# Delibird.net
KiCad netlist of a schematic drawn in Altium Designer
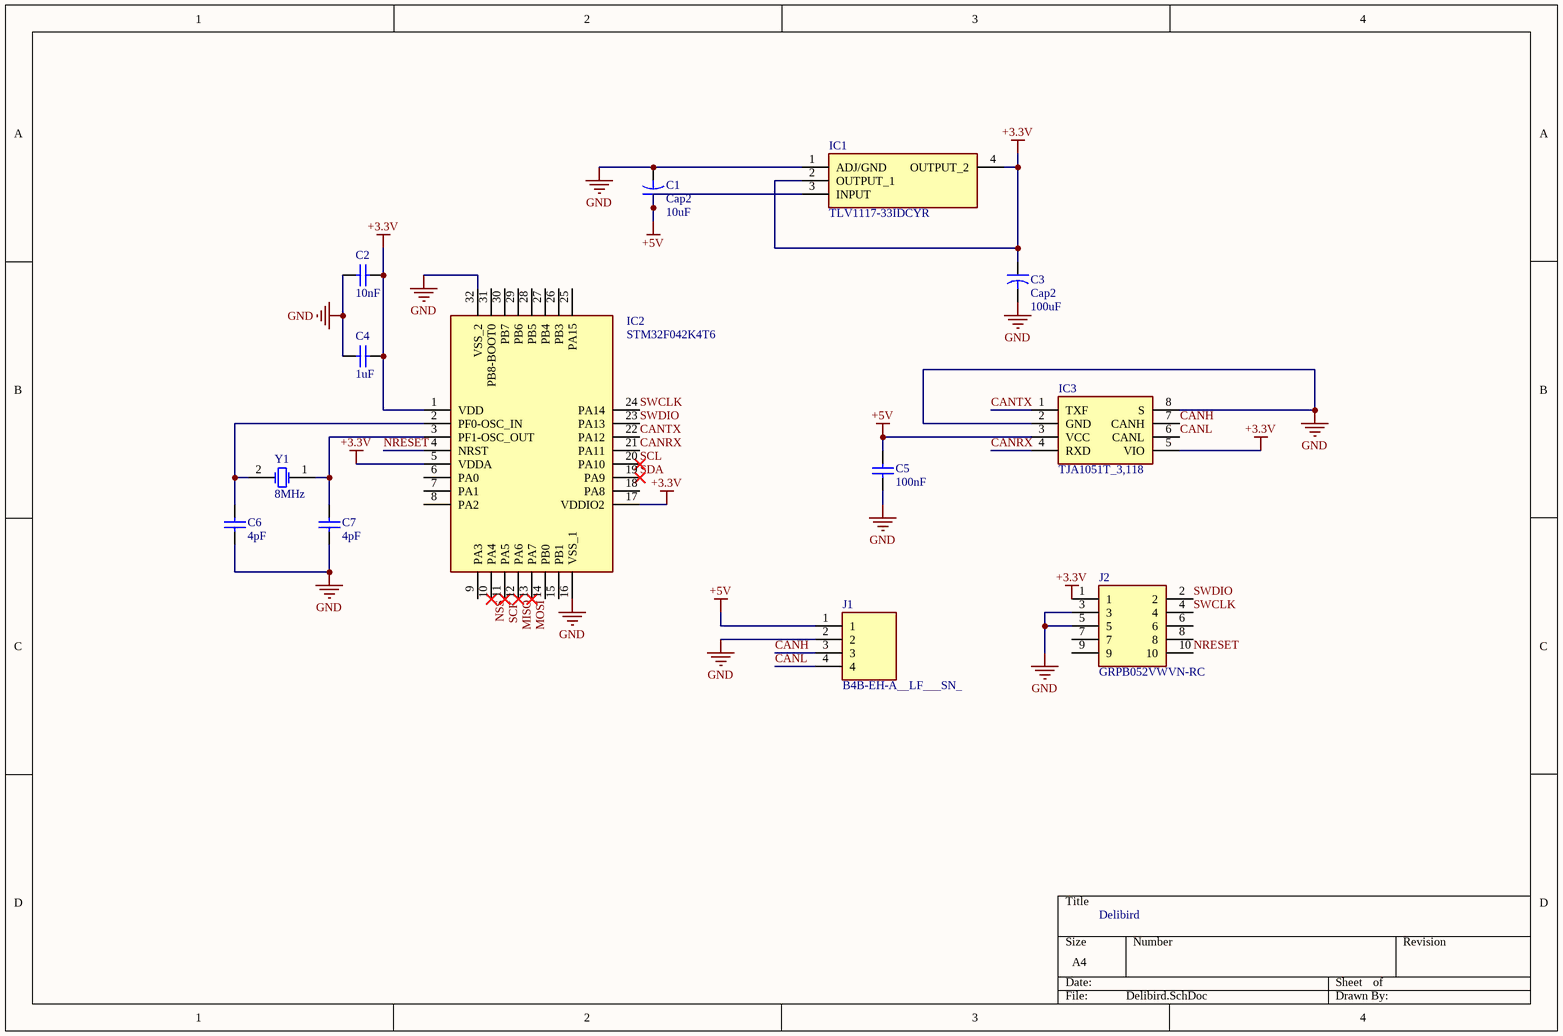
[diagram p0: Delibird.SchDoc]

(export (version "E")
  (design (tool "Eeschema 10.0.6"))
  (components
    (comp (ref "C1")
      (value "Cap2")
      (footprint "C0805")
      (description "Capacitor")
      (fields (field (name "ALTIUM_VALUE") "10uF") (field (name "PUBLISHER") "Altium Limited"))
      (libsource (lib "Miscellaneous Devices") (part "Cap2"))
    )
    (comp (ref "C2")
      (value "10nF")
      (footprint "0805 - Capacitor")
      (description "Nonpolarized Capacitor")
      (fields (field (name "Comment") "Capacitor - Nonpolarized"))
      (libsource (lib "General") (part "Capacitor - Nonpolarized"))
    )
    (comp (ref "C3")
      (value "Cap2")
      (footprint "C0805")
      (description "Capacitor")
      (fields (field (name "ALTIUM_VALUE") "100uF") (field (name "PUBLISHER") "Altium Limited"))
      (libsource (lib "Miscellaneous Devices") (part "Cap2"))
    )
    (comp (ref "C4")
      (value "1uF")
      (footprint "0805 - Capacitor")
      (description "Nonpolarized Capacitor")
      (fields (field (name "Comment") "Capacitor - Nonpolarized"))
      (libsource (lib "General") (part "Capacitor - Nonpolarized"))
    )
    (comp (ref "C5")
      (value "100nF")
      (footprint "0805 - Capacitor")
      (description "Nonpolarized Capacitor")
      (fields (field (name "Comment") "Capacitor - Nonpolarized"))
      (libsource (lib "General") (part "Capacitor - Nonpolarized"))
    )
    (comp (ref "C6")
      (value "4pF")
      (footprint "0805 - Capacitor")
      (description "Nonpolarized Capacitor")
      (fields (field (name "Comment") "Capacitor - Nonpolarized"))
      (libsource (lib "General") (part "Capacitor - Nonpolarized"))
    )
    (comp (ref "C7")
      (value "4pF")
      (footprint "0805 - Capacitor")
      (description "Nonpolarized Capacitor")
      (fields (field (name "Comment") "Capacitor - Nonpolarized"))
      (libsource (lib "General") (part "Capacitor - Nonpolarized"))
    )
    (comp (ref "IC1")
      (value "TLV1117-33IDCYR")
      (footprint "Embedded:SOT230P700X180-4N")
      (description "Integrated Circuit")
      (fields
        (field (name "MANUFACTURER_PART_NUMBER") "TLV1117-33CDCYR")
        (field (name "MOUSER PART NUMBER") "595-TLV1117-33CDCYR")
      )
      (libsource (lib "*") (part "TLV1117-33CDCYR"))
    )
    (comp (ref "IC2")
      (value "STM32F042K4T6")
      (footprint "Embedded:QFP80P900X900X160-32N")
      (description "Integrated Circuit")
      (fields (field (name "MOUSER PART NUMBER") "511-STM32F042K4T6"))
      (libsource (lib "*") (part "STM32F042K4T6"))
    )
    (comp (ref "IC3")
      (value "TJA1051T_3,118")
      (footprint "Embedded:SOIC127P600X175-8N")
      (description "Integrated Circuit")
      (fields
        (field (name "MANUFACTURER_PART_NUMBER") "TJA1051T/3,118")
        (field (name "MOUSER PART NUMBER") "771-TJA1051T3118")
      )
      (libsource (lib "Embedded") (part "TJA1051T_3,118"))
    )
    (comp (ref "J1")
      (value "B4B-EH-A__LF___SN_")
      (footprint "Embedded:SHDR4W64P0X250_1X4_1250X380X600P")
      (description "Connector")
      (fields (field (name "MANUFACTURER_PART_NUMBER") "B4B-EH-A (LF) (SN)"))
      (libsource (lib "*") (part "B4B-EH-A__LF___SN_"))
    )
    (comp (ref "J2")
      (value "GRPB052VWVN-RC")
      (footprint "Embedded:HDRV10W50P127_2X5_635X340X430P")
      (description "Connector")
      (libsource (lib "Embedded") (part "GRPB052VWVN-RC"))
    )
    (comp (ref "Y1")
      (value "8MHz")
      (footprint "CX5032GB08000H0HPQZ1")
      (description "Crystal Oscillator")
      (fields (field (name "MANUFACTURER") "CX5032GB08000H0HPQZ1") (field (name "Comment") "Oscillator"))
      (libsource (lib "General") (part "Oscillator"))
    )
  )
  (nets
    (net (code "1") (name "+3.3V") (class "Default")
      (node (ref "C2") (pin "1") (pinfunction "1_1") (pintype "passive"))
      (node (ref "C3") (pin "1") (pinfunction "1_1") (pintype "passive"))
      (node (ref "C4") (pin "1") (pinfunction "1_1") (pintype "passive"))
      (node (ref "IC1") (pin "2") (pinfunction "OUTPUT_1_2") (pintype "passive"))
      (node (ref "IC1") (pin "4") (pinfunction "OUTPUT_2_4") (pintype "passive"))
      (node (ref "IC2") (pin "1") (pinfunction "VDD_1") (pintype "passive"))
      (node (ref "IC2") (pin "17") (pinfunction "VDDIO2_17") (pintype "passive"))
      (node (ref "IC2") (pin "5") (pinfunction "VDDA_5") (pintype "passive"))
      (node (ref "IC3") (pin "5") (pinfunction "VIO_5") (pintype "passive"))
      (node (ref "J2") (pin "1") (pinfunction "1_1") (pintype "passive"))
    )
    (net (code "2") (name "+5V") (class "Default")
      (node (ref "C1") (pin "1") (pinfunction "1_1") (pintype "passive"))
      (node (ref "C5") (pin "1") (pinfunction "1_1") (pintype "passive"))
      (node (ref "IC1") (pin "3") (pinfunction "INPUT_3") (pintype "passive"))
      (node (ref "IC3") (pin "3") (pinfunction "VCC_3") (pintype "passive"))
      (node (ref "J1") (pin "1") (pinfunction "1_1") (pintype "passive"))
    )
    (net (code "3") (name "/CANH") (class "Default")
      (node (ref "IC3") (pin "7") (pinfunction "CANH_7") (pintype "passive"))
      (node (ref "J1") (pin "3") (pinfunction "3_3") (pintype "passive"))
    )
    (net (code "4") (name "/CANL") (class "Default")
      (node (ref "IC3") (pin "6") (pinfunction "CANL_6") (pintype "passive"))
      (node (ref "J1") (pin "4") (pinfunction "4_4") (pintype "passive"))
    )
    (net (code "5") (name "/CANRX") (class "Default")
      (node (ref "IC2") (pin "21") (pinfunction "PA11_21") (pintype "passive"))
      (node (ref "IC3") (pin "4") (pinfunction "RXD_4") (pintype "passive"))
    )
    (net (code "6") (name "/CANTX") (class "Default")
      (node (ref "IC2") (pin "22") (pinfunction "PA12_22") (pintype "passive"))
      (node (ref "IC3") (pin "1") (pinfunction "TXF_1") (pintype "passive"))
    )
    (net (code "7") (name "/MISO") (class "Default")
      (node (ref "IC2") (pin "12") (pinfunction "PA6_12") (pintype "passive+no_connect"))
    )
    (net (code "8") (name "/MOSI") (class "Default")
      (node (ref "IC2") (pin "13") (pinfunction "PA7_13") (pintype "passive+no_connect"))
    )
    (net (code "9") (name "/NRESET") (class "Default")
      (node (ref "IC2") (pin "4") (pinfunction "NRST_4") (pintype "passive"))
      (node (ref "J2") (pin "10") (pinfunction "10_10") (pintype "passive"))
    )
    (net (code "10") (name "/NSS") (class "Default")
      (node (ref "IC2") (pin "10") (pinfunction "PA4_10") (pintype "passive+no_connect"))
    )
    (net (code "11") (name "/SCK") (class "Default")
      (node (ref "IC2") (pin "11") (pinfunction "PA5_11") (pintype "passive+no_connect"))
    )
    (net (code "12") (name "/SCL") (class "Default")
      (node (ref "IC2") (pin "20") (pinfunction "PA10_20") (pintype "passive+no_connect"))
    )
    (net (code "13") (name "/SDA") (class "Default")
      (node (ref "IC2") (pin "19") (pinfunction "PA9_19") (pintype "passive+no_connect"))
    )
    (net (code "14") (name "/SWCLK") (class "Default")
      (node (ref "IC2") (pin "24") (pinfunction "PA14_24") (pintype "passive"))
      (node (ref "J2") (pin "4") (pinfunction "4_4") (pintype "passive"))
    )
    (net (code "15") (name "/SWDIO") (class "Default")
      (node (ref "IC2") (pin "23") (pinfunction "PA13_23") (pintype "passive"))
      (node (ref "J2") (pin "2") (pinfunction "2_2") (pintype "passive"))
    )
    (net (code "16") (name "GND") (class "Default")
      (node (ref "C1") (pin "2") (pinfunction "2_2") (pintype "passive"))
      (node (ref "C2") (pin "2") (pinfunction "2_2") (pintype "passive"))
      (node (ref "C3") (pin "2") (pinfunction "2_2") (pintype "passive"))
      (node (ref "C4") (pin "2") (pinfunction "2_2") (pintype "passive"))
      (node (ref "C5") (pin "2") (pinfunction "2_2") (pintype "passive"))
      (node (ref "C6") (pin "1") (pinfunction "1_1") (pintype "passive"))
      (node (ref "C7") (pin "1") (pinfunction "1_1") (pintype "passive"))
      (node (ref "IC1") (pin "1") (pinfunction "ADJ/GND_1") (pintype "passive"))
      (node (ref "IC2") (pin "16") (pinfunction "VSS_1_16") (pintype "passive"))
      (node (ref "IC2") (pin "32") (pinfunction "VSS_2_32") (pintype "passive"))
      (node (ref "IC3") (pin "2") (pinfunction "GND_2") (pintype "passive"))
      (node (ref "IC3") (pin "8") (pinfunction "S_8") (pintype "passive"))
      (node (ref "J1") (pin "2") (pinfunction "2_2") (pintype "passive"))
      (node (ref "J2") (pin "3") (pinfunction "3_3") (pintype "passive"))
      (node (ref "J2") (pin "5") (pinfunction "5_5") (pintype "passive"))
    )
    (net (code "17") (name "Net-(IC2-PF0-OSC_IN)") (class "Default")
      (node (ref "C6") (pin "2") (pinfunction "2_2") (pintype "passive"))
      (node (ref "IC2") (pin "2") (pinfunction "PF0-OSC_IN_2") (pintype "passive"))
      (node (ref "Y1") (pin "2") (pinfunction "OSC2_2") (pintype "passive"))
    )
    (net (code "18") (name "Net-(IC2-PF1-OSC_OUT)") (class "Default")
      (node (ref "C7") (pin "2") (pinfunction "2_2") (pintype "passive"))
      (node (ref "IC2") (pin "3") (pinfunction "PF1-OSC_OUT_3") (pintype "passive"))
      (node (ref "Y1") (pin "1") (pinfunction "OSC1_1") (pintype "passive"))
    )
    (net (code "19") (name "unconnected-(IC2-PA0-Pad6)") (class "Default")
      (node (ref "IC2") (pin "6") (pinfunction "PA0_6") (pintype "passive"))
    )
    (net (code "20") (name "unconnected-(IC2-PA1-Pad7)") (class "Default")
      (node (ref "IC2") (pin "7") (pinfunction "PA1_7") (pintype "passive"))
    )
    (net (code "21") (name "unconnected-(IC2-PA2-Pad8)") (class "Default")
      (node (ref "IC2") (pin "8") (pinfunction "PA2_8") (pintype "passive"))
    )
    (net (code "22") (name "unconnected-(IC2-PA3-Pad9)") (class "Default")
      (node (ref "IC2") (pin "9") (pinfunction "PA3_9") (pintype "passive"))
    )
    (net (code "23") (name "unconnected-(IC2-PA8-Pad18)") (class "Default")
      (node (ref "IC2") (pin "18") (pinfunction "PA8_18") (pintype "passive"))
    )
    (net (code "24") (name "unconnected-(IC2-PA15-Pad25)") (class "Default")
      (node (ref "IC2") (pin "25") (pinfunction "PA15_25") (pintype "passive"))
    )
    (net (code "25") (name "unconnected-(IC2-PB0-Pad14)") (class "Default")
      (node (ref "IC2") (pin "14") (pinfunction "PB0_14") (pintype "passive"))
    )
    (net (code "26") (name "unconnected-(IC2-PB1-Pad15)") (class "Default")
      (node (ref "IC2") (pin "15") (pinfunction "PB1_15") (pintype "passive"))
    )
    (net (code "27") (name "unconnected-(IC2-PB3-Pad26)") (class "Default")
      (node (ref "IC2") (pin "26") (pinfunction "PB3_26") (pintype "passive"))
    )
    (net (code "28") (name "unconnected-(IC2-PB4-Pad27)") (class "Default")
      (node (ref "IC2") (pin "27") (pinfunction "PB4_27") (pintype "passive"))
    )
    (net (code "29") (name "unconnected-(IC2-PB5-Pad28)") (class "Default")
      (node (ref "IC2") (pin "28") (pinfunction "PB5_28") (pintype "passive"))
    )
    (net (code "30") (name "unconnected-(IC2-PB6-Pad29)") (class "Default")
      (node (ref "IC2") (pin "29") (pinfunction "PB6_29") (pintype "passive"))
    )
    (net (code "31") (name "unconnected-(IC2-PB7-Pad30)") (class "Default")
      (node (ref "IC2") (pin "30") (pinfunction "PB7_30") (pintype "passive"))
    )
    (net (code "32") (name "unconnected-(IC2-PB8-BOOT0-Pad31)") (class "Default")
      (node (ref "IC2") (pin "31") (pinfunction "PB8-BOOT0_31") (pintype "passive"))
    )
    (net (code "33") (name "unconnected-(J2-Pad6)") (class "Default")
      (node (ref "J2") (pin "6") (pinfunction "6_6") (pintype "passive"))
    )
    (net (code "34") (name "unconnected-(J2-Pad7)") (class "Default")
      (node (ref "J2") (pin "7") (pinfunction "7_7") (pintype "passive"))
    )
    (net (code "35") (name "unconnected-(J2-Pad8)") (class "Default")
      (node (ref "J2") (pin "8") (pinfunction "8_8") (pintype "passive"))
    )
    (net (code "36") (name "unconnected-(J2-Pad9)") (class "Default")
      (node (ref "J2") (pin "9") (pinfunction "9_9") (pintype "passive"))
    )
  )
)
